# usb_to_uart_swd_bridge.net
KiCad netlist of a schematic drawn in Altium Designer
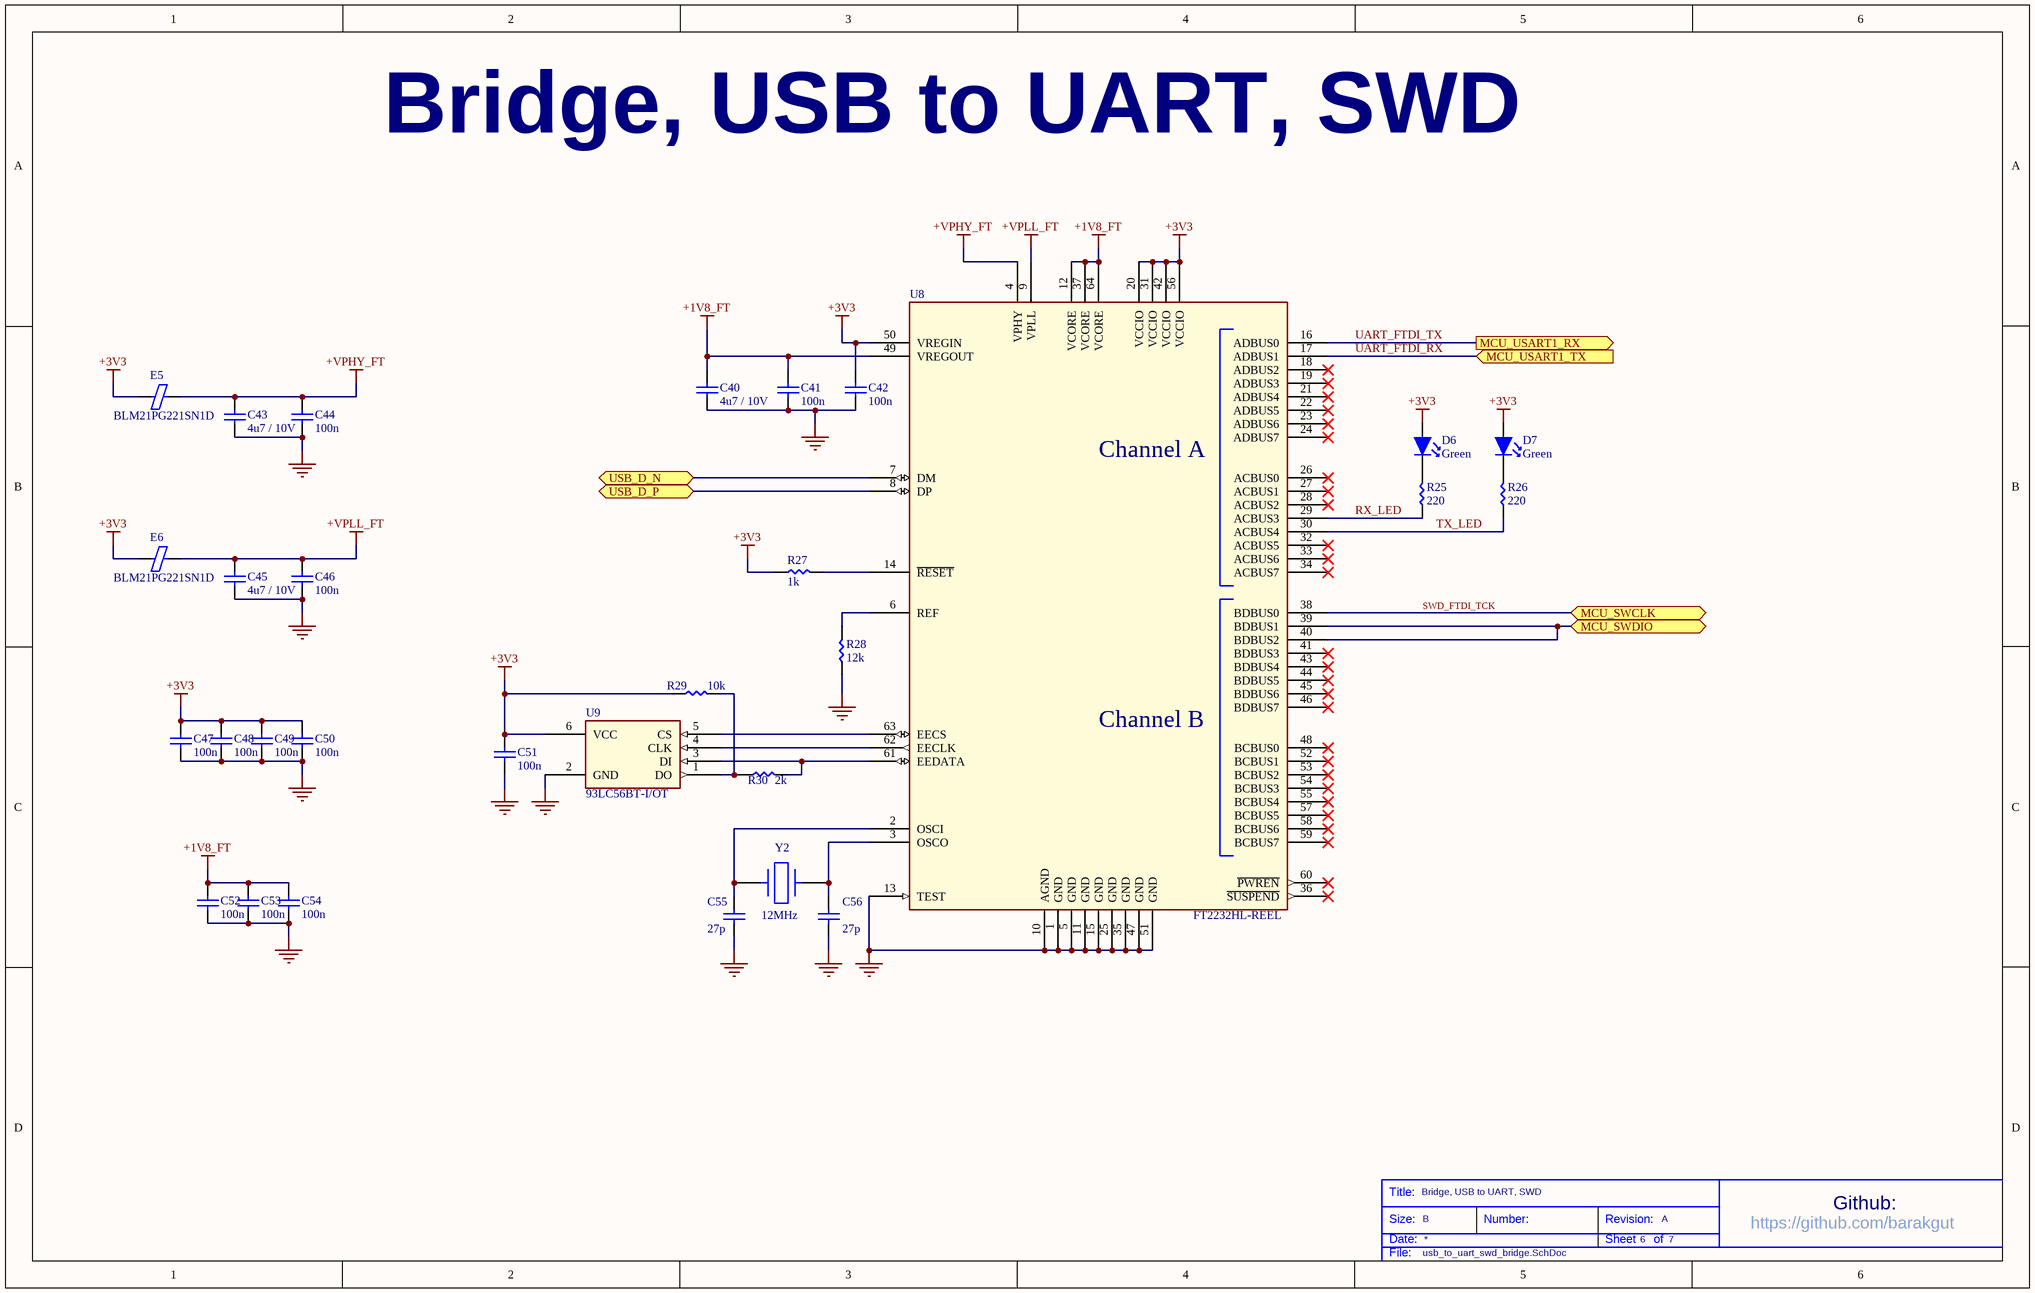
[diagram p0: usb_to_uart_swd_bridge.SchDoc]

(export (version "E")
  (design (tool "Eeschema 10.0.6"))
  (components
    (comp (ref "C40")
      (value "4u7 / 10V")
      (footprint "C0805")
      (fields
        (field (name "MANUFACTURER") "TDK")
        (field (name "TOLERANCE") "±10%")
        (field (name "MANUFACTURER PART NUMBER") "C2012X7R1A475K085AC")
      )
      (libsource (lib "rookieboard_symbols") (part "C2012X7R1A475K085AC"))
    )
    (comp (ref "C41")
      (value "100n")
      (footprint "C0402")
      (fields
        (field (name "MANUFACTURER") "TDK")
        (field (name "PCN PART NUMBER") "MLCC Part Number Change 30/Nov/2012")
        (field (name "TOLERANCE") "±10%")
      )
      (libsource (lib "rookieboard_symbols") (part "CGA2B3X7R1E104K050BB"))
    )
    (comp (ref "C42")
      (value "100n")
      (footprint "C0402")
      (fields
        (field (name "MANUFACTURER") "TDK")
        (field (name "PCN PART NUMBER") "MLCC Part Number Change 30/Nov/2012")
        (field (name "TOLERANCE") "±10%")
      )
      (libsource (lib "rookieboard_symbols") (part "CGA2B3X7R1E104K050BB"))
    )
    (comp (ref "C43")
      (value "4u7 / 10V")
      (footprint "C0805")
      (fields
        (field (name "MANUFACTURER") "TDK")
        (field (name "TOLERANCE") "±10%")
        (field (name "MANUFACTURER PART NUMBER") "C2012X7R1A475K085AC")
      )
      (libsource (lib "rookieboard_symbols") (part "C2012X7R1A475K085AC"))
    )
    (comp (ref "C44")
      (value "100n")
      (footprint "C0402")
      (fields
        (field (name "MANUFACTURER") "TDK")
        (field (name "PCN PART NUMBER") "MLCC Part Number Change 30/Nov/2012")
        (field (name "TOLERANCE") "±10%")
      )
      (libsource (lib "rookieboard_symbols") (part "CGA2B3X7R1E104K050BB"))
    )
    (comp (ref "C45")
      (value "4u7 / 10V")
      (footprint "C0805")
      (fields
        (field (name "MANUFACTURER") "TDK")
        (field (name "TOLERANCE") "±10%")
        (field (name "MANUFACTURER PART NUMBER") "C2012X7R1A475K085AC")
      )
      (libsource (lib "rookieboard_symbols") (part "C2012X7R1A475K085AC"))
    )
    (comp (ref "C46")
      (value "100n")
      (footprint "C0402")
      (fields
        (field (name "MANUFACTURER") "TDK")
        (field (name "PCN PART NUMBER") "MLCC Part Number Change 30/Nov/2012")
        (field (name "TOLERANCE") "±10%")
      )
      (libsource (lib "rookieboard_symbols") (part "CGA2B3X7R1E104K050BB"))
    )
    (comp (ref "C47")
      (value "100n")
      (footprint "C0402")
      (fields
        (field (name "MANUFACTURER") "TDK")
        (field (name "PCN PART NUMBER") "MLCC Part Number Change 30/Nov/2012")
        (field (name "TOLERANCE") "±10%")
      )
      (libsource (lib "rookieboard_symbols") (part "CGA2B3X7R1E104K050BB"))
    )
    (comp (ref "C48")
      (value "100n")
      (footprint "C0402")
      (fields
        (field (name "MANUFACTURER") "TDK")
        (field (name "PCN PART NUMBER") "MLCC Part Number Change 30/Nov/2012")
        (field (name "TOLERANCE") "±10%")
      )
      (libsource (lib "rookieboard_symbols") (part "CGA2B3X7R1E104K050BB"))
    )
    (comp (ref "C49")
      (value "100n")
      (footprint "C0402")
      (fields
        (field (name "MANUFACTURER") "TDK")
        (field (name "PCN PART NUMBER") "MLCC Part Number Change 30/Nov/2012")
        (field (name "TOLERANCE") "±10%")
      )
      (libsource (lib "rookieboard_symbols") (part "CGA2B3X7R1E104K050BB"))
    )
    (comp (ref "C50")
      (value "100n")
      (footprint "C0402")
      (fields
        (field (name "MANUFACTURER") "TDK")
        (field (name "PCN PART NUMBER") "MLCC Part Number Change 30/Nov/2012")
        (field (name "TOLERANCE") "±10%")
      )
      (libsource (lib "rookieboard_symbols") (part "CGA2B3X7R1E104K050BB"))
    )
    (comp (ref "C51")
      (value "100n")
      (footprint "C0402")
      (fields
        (field (name "MANUFACTURER") "TDK")
        (field (name "PCN PART NUMBER") "MLCC Part Number Change 30/Nov/2012")
        (field (name "TOLERANCE") "±10%")
      )
      (libsource (lib "rookieboard_symbols") (part "CGA2B3X7R1E104K050BB"))
    )
    (comp (ref "C52")
      (value "100n")
      (footprint "C0402")
      (fields
        (field (name "MANUFACTURER") "TDK")
        (field (name "PCN PART NUMBER") "MLCC Part Number Change 30/Nov/2012")
        (field (name "TOLERANCE") "±10%")
      )
      (libsource (lib "rookieboard_symbols") (part "CGA2B3X7R1E104K050BB"))
    )
    (comp (ref "C53")
      (value "100n")
      (footprint "C0402")
      (fields
        (field (name "MANUFACTURER") "TDK")
        (field (name "PCN PART NUMBER") "MLCC Part Number Change 30/Nov/2012")
        (field (name "TOLERANCE") "±10%")
      )
      (libsource (lib "rookieboard_symbols") (part "CGA2B3X7R1E104K050BB"))
    )
    (comp (ref "C54")
      (value "100n")
      (footprint "C0402")
      (fields
        (field (name "MANUFACTURER") "TDK")
        (field (name "PCN PART NUMBER") "MLCC Part Number Change 30/Nov/2012")
        (field (name "TOLERANCE") "±10%")
      )
      (libsource (lib "rookieboard_symbols") (part "CGA2B3X7R1E104K050BB"))
    )
    (comp (ref "C55")
      (value "27p")
      (footprint "C0402")
      (fields
        (field (name "MANUFACTURER") "Murata")
        (field (name "MANUFACTURER PART NUMBER") "GJM1555C1H270FB01D")
      )
      (libsource (lib "rookieboard_symbols") (part "GJM1555C1H270FB01D"))
    )
    (comp (ref "C56")
      (value "27p")
      (footprint "C0402")
      (fields
        (field (name "MANUFACTURER") "Murata")
        (field (name "MANUFACTURER PART NUMBER") "GJM1555C1H270FB01D")
      )
      (libsource (lib "rookieboard_symbols") (part "GJM1555C1H270FB01D"))
    )
    (comp (ref "D6")
      (value "Green")
      (footprint "150141VS73100_LED")
      (description "WURTH ELEKTRONIK   150141VS73100   LED, GREEN, 90MCD, 570NM")
      (fields
        (field (name "MANUFACTURER") "Wurth Electronics")
        (field (name "MANUFACTURER PART NUMBER") "150141VS73100")
      )
      (libsource (lib "rookieboard_symbols") (part "150141VS73100"))
    )
    (comp (ref "D7")
      (value "Green")
      (footprint "150141VS73100_LED")
      (description "WURTH ELEKTRONIK   150141VS73100   LED, GREEN, 90MCD, 570NM")
      (fields
        (field (name "MANUFACTURER") "Wurth Electronics")
        (field (name "MANUFACTURER PART NUMBER") "150141VS73100")
      )
      (libsource (lib "rookieboard_symbols") (part "150141VS73100"))
    )
    (comp (ref "E5")
      (value "BLM21PG221SN1D")
      (footprint "R0805")
      (description "FERRITE CHIP 220 OHM 0805")
      (fields (field (name "MANUFACTURER") "Murata"))
      (libsource (lib "rookieboard_symbols") (part "BLM21PG221SN1D"))
    )
    (comp (ref "E6")
      (value "BLM21PG221SN1D")
      (footprint "R0805")
      (description "FERRITE CHIP 220 OHM 0805")
      (fields (field (name "MANUFACTURER") "Murata"))
      (libsource (lib "rookieboard_symbols") (part "BLM21PG221SN1D"))
    )
    (comp (ref "R25")
      (value "220")
      (footprint "R0805")
      (description "Thick Film Resistors - SMD 1/8W 220ohm 1%")
      (fields (field (name "MANUFACTURER") "Yageo") (field (name "TOLERANCE") "1 %"))
      (libsource (lib "rookieboard_symbols") (part "AC0805FR-07220RL"))
    )
    (comp (ref "R26")
      (value "220")
      (footprint "R0805")
      (description "Thick Film Resistors - SMD 1/8W 220ohm 1%")
      (fields (field (name "MANUFACTURER") "Yageo") (field (name "TOLERANCE") "1 %"))
      (libsource (lib "rookieboard_symbols") (part "AC0805FR-07220RL"))
    )
    (comp (ref "R27")
      (value "1k")
      (footprint "R0805")
      (description "RES SMD 1K OHM 1% 1/8W 0805")
      (fields (field (name "MANUFACTURER") "Yageo") (field (name "TOLERANCE") "1 %"))
      (libsource (lib "rookieboard_symbols") (part "RC0805FR-071KL"))
    )
    (comp (ref "R28")
      (value "12k")
      (footprint "R0805")
      (fields
        (field (name "MANUFACTURER") "Yageo")
        (field (name "MANUFACTURER PART NUMBER") "AC0805FR-0712KL")
      )
      (libsource (lib "rookieboard_symbols") (part "AC0805FR-0712KL"))
    )
    (comp (ref "R29")
      (value "10k")
      (footprint "R0805")
      (description "RES SMD 10K OHM 1% 1/8W 0805")
      (fields (field (name "MANUFACTURER") "Yageo") (field (name "TOLERANCE") "1 %"))
      (libsource (lib "rookieboard_symbols") (part "RC0805FR-0710KL"))
    )
    (comp (ref "R30")
      (value "2k")
      (footprint "R0805")
      (description "RES SMD 2K OHM 1% 1/8W 0805")
      (fields (field (name "MANUFACTURER") "Yageo") (field (name "TOLERANCE") "1 %"))
      (libsource (lib "rookieboard_symbols") (part "RC0805FR-072KL"))
    )
    (comp (ref "U8")
      (value "FT2232HL-REEL")
      (footprint "LQFP64")
      (description "IC USB HS DUAL UART/FIFO 64-LQFP")
      (fields (field (name "MANUFACTURER") "FTDI"))
      (libsource (lib "rookieboard_symbols") (part "FT2232HL-REEL"))
    )
    (comp (ref "U9")
      (value "93LC56BT-I/OT")
      (footprint "SOT-23-6")
      (description "EEPROM 128x16")
      (fields (field (name "MANUFACTURER") "Microchip"))
      (libsource (lib "rookieboard_symbols") (part "93LC56BT-I/OT"))
    )
    (comp (ref "Y2")
      (value "12MHz")
      (footprint "ABLS7M2-12.000MHZ-D-2Y-T")
      (description "Crystals 12.0MHz 18pF 30ppm -40C +85C")
      (fields
        (field (name "MANUFACTURER") "Abracon")
        (field (name "MANUFACTURER PART NUMBER") "ABLS7M2-12.000MHZ-D-2Y-T")
      )
      (libsource (lib "rookieboard_symbols") (part "ABLS7M2-12.000MHZ-D-2Y-T"))
    )
  )
  (nets
    (net (code "1") (name "+1V8_FT") (class "Default")
      (node (ref "C40") (pin "2") (pinfunction "2_2") (pintype "passive"))
      (node (ref "C41") (pin "2") (pinfunction "2_2") (pintype "passive"))
      (node (ref "C52") (pin "2") (pinfunction "2_2") (pintype "passive"))
      (node (ref "C53") (pin "2") (pinfunction "2_2") (pintype "passive"))
      (node (ref "C54") (pin "2") (pinfunction "2_2") (pintype "passive"))
      (node (ref "U8") (pin "12") (pinfunction "VCORE_12") (pintype "power_in"))
      (node (ref "U8") (pin "37") (pinfunction "VCORE_37") (pintype "power_in"))
      (node (ref "U8") (pin "49") (pinfunction "VREGOUT_49") (pintype "power_in"))
      (node (ref "U8") (pin "64") (pinfunction "VCORE_64") (pintype "power_in"))
    )
    (net (code "2") (name "+3V3") (class "Default")
      (node (ref "C42") (pin "2") (pinfunction "2_2") (pintype "passive"))
      (node (ref "C47") (pin "2") (pinfunction "2_2") (pintype "passive"))
      (node (ref "C48") (pin "2") (pinfunction "2_2") (pintype "passive"))
      (node (ref "C49") (pin "2") (pinfunction "2_2") (pintype "passive"))
      (node (ref "C50") (pin "2") (pinfunction "2_2") (pintype "passive"))
      (node (ref "C51") (pin "2") (pinfunction "2_2") (pintype "passive"))
      (node (ref "D6") (pin "2") (pinfunction "A_2") (pintype "passive"))
      (node (ref "D7") (pin "2") (pinfunction "A_2") (pintype "passive"))
      (node (ref "E5") (pin "1") (pinfunction "1_1") (pintype "passive"))
      (node (ref "E6") (pin "1") (pinfunction "1_1") (pintype "passive"))
      (node (ref "R27") (pin "1") (pinfunction "1_1") (pintype "passive"))
      (node (ref "R29") (pin "1") (pinfunction "1_1") (pintype "passive"))
      (node (ref "U8") (pin "20") (pinfunction "VCCIO_20") (pintype "power_in"))
      (node (ref "U8") (pin "31") (pinfunction "VCCIO_31") (pintype "power_in"))
      (node (ref "U8") (pin "42") (pinfunction "VCCIO_42") (pintype "power_in"))
      (node (ref "U8") (pin "50") (pinfunction "VREGIN_50") (pintype "power_in"))
      (node (ref "U8") (pin "56") (pinfunction "VCCIO_56") (pintype "power_in"))
      (node (ref "U9") (pin "6") (pinfunction "VCC_6") (pintype "power_in"))
    )
    (net (code "3") (name "+VPHY_FT") (class "Default")
      (node (ref "C43") (pin "2") (pinfunction "2_2") (pintype "passive"))
      (node (ref "C44") (pin "2") (pinfunction "2_2") (pintype "passive"))
      (node (ref "E5") (pin "2") (pinfunction "2_2") (pintype "passive"))
      (node (ref "U8") (pin "4") (pinfunction "VPHY_4") (pintype "power_in"))
    )
    (net (code "4") (name "+VPLL_FT") (class "Default")
      (node (ref "C45") (pin "2") (pinfunction "2_2") (pintype "passive"))
      (node (ref "C46") (pin "2") (pinfunction "2_2") (pintype "passive"))
      (node (ref "E6") (pin "2") (pinfunction "2_2") (pintype "passive"))
      (node (ref "U8") (pin "9") (pinfunction "VPLL_9") (pintype "power_in"))
    )
    (net (code "5") (name "/MCU_SWDIO") (class "Default")
      (node (ref "U8") (pin "39") (pinfunction "BDBUS1_39") (pintype "passive"))
      (node (ref "U8") (pin "40") (pinfunction "BDBUS2_40") (pintype "passive"))
    )
    (net (code "6") (name "/RX_LED") (class "Default")
      (node (ref "R25") (pin "1") (pinfunction "1_1") (pintype "passive"))
      (node (ref "U8") (pin "29") (pinfunction "ACBUS3_29") (pintype "passive"))
    )
    (net (code "7") (name "/SWD_FTDI_TCK") (class "Default")
      (node (ref "U8") (pin "38") (pinfunction "BDBUS0_38") (pintype "passive"))
    )
    (net (code "8") (name "/TX_LED") (class "Default")
      (node (ref "R26") (pin "1") (pinfunction "1_1") (pintype "passive"))
      (node (ref "U8") (pin "30") (pinfunction "ACBUS4_30") (pintype "passive"))
    )
    (net (code "9") (name "/UART_FTDI_RX") (class "Default")
      (node (ref "U8") (pin "17") (pinfunction "ADBUS1_17") (pintype "passive"))
    )
    (net (code "10") (name "/UART_FTDI_TX") (class "Default")
      (node (ref "U8") (pin "16") (pinfunction "ADBUS0_16") (pintype "passive"))
    )
    (net (code "11") (name "/USB_D_N") (class "Default")
      (node (ref "U8") (pin "7") (pinfunction "DM_7") (pintype "bidirectional"))
    )
    (net (code "12") (name "/USB_D_P") (class "Default")
      (node (ref "U8") (pin "8") (pinfunction "DP_8") (pintype "bidirectional"))
    )
    (net (code "13") (name "GND") (class "Default")
      (node (ref "C40") (pin "1") (pinfunction "1_1") (pintype "passive"))
      (node (ref "C41") (pin "1") (pinfunction "1_1") (pintype "passive"))
      (node (ref "C42") (pin "1") (pinfunction "1_1") (pintype "passive"))
      (node (ref "C43") (pin "1") (pinfunction "1_1") (pintype "passive"))
      (node (ref "C44") (pin "1") (pinfunction "1_1") (pintype "passive"))
      (node (ref "C45") (pin "1") (pinfunction "1_1") (pintype "passive"))
      (node (ref "C46") (pin "1") (pinfunction "1_1") (pintype "passive"))
      (node (ref "C47") (pin "1") (pinfunction "1_1") (pintype "passive"))
      (node (ref "C48") (pin "1") (pinfunction "1_1") (pintype "passive"))
      (node (ref "C49") (pin "1") (pinfunction "1_1") (pintype "passive"))
      (node (ref "C50") (pin "1") (pinfunction "1_1") (pintype "passive"))
      (node (ref "C51") (pin "1") (pinfunction "1_1") (pintype "passive"))
      (node (ref "C52") (pin "1") (pinfunction "1_1") (pintype "passive"))
      (node (ref "C53") (pin "1") (pinfunction "1_1") (pintype "passive"))
      (node (ref "C54") (pin "1") (pinfunction "1_1") (pintype "passive"))
      (node (ref "C55") (pin "1") (pinfunction "1_1") (pintype "passive"))
      (node (ref "C56") (pin "1") (pinfunction "1_1") (pintype "passive"))
      (node (ref "R28") (pin "1") (pinfunction "1_1") (pintype "passive"))
      (node (ref "U8") (pin "1") (pinfunction "GND_1") (pintype "power_in"))
      (node (ref "U8") (pin "10") (pinfunction "AGND_10") (pintype "power_in"))
      (node (ref "U8") (pin "11") (pinfunction "GND_11") (pintype "power_in"))
      (node (ref "U8") (pin "13") (pinfunction "TEST_13") (pintype "input"))
      (node (ref "U8") (pin "15") (pinfunction "GND_15") (pintype "power_in"))
      (node (ref "U8") (pin "25") (pinfunction "GND_25") (pintype "power_in"))
      (node (ref "U8") (pin "35") (pinfunction "GND_35") (pintype "power_in"))
      (node (ref "U8") (pin "47") (pinfunction "GND_47") (pintype "power_in"))
      (node (ref "U8") (pin "5") (pinfunction "GND_5") (pintype "power_in"))
      (node (ref "U8") (pin "51") (pinfunction "GND_51") (pintype "power_in"))
      (node (ref "U9") (pin "2") (pinfunction "GND_2") (pintype "power_in"))
    )
    (net (code "14") (name "Net-(D6-K)") (class "Default")
      (node (ref "D6") (pin "1") (pinfunction "K_1") (pintype "passive"))
      (node (ref "R25") (pin "2") (pinfunction "2_2") (pintype "passive"))
    )
    (net (code "15") (name "Net-(D7-K)") (class "Default")
      (node (ref "D7") (pin "1") (pinfunction "K_1") (pintype "passive"))
      (node (ref "R26") (pin "2") (pinfunction "2_2") (pintype "passive"))
    )
    (net (code "16") (name "Net-(U8-EECLK)") (class "Default")
      (node (ref "U8") (pin "62") (pinfunction "EECLK_62") (pintype "output"))
      (node (ref "U9") (pin "4") (pinfunction "CLK_4") (pintype "input"))
    )
    (net (code "17") (name "Net-(U8-EECS)") (class "Default")
      (node (ref "U8") (pin "63") (pinfunction "EECS_63") (pintype "bidirectional"))
      (node (ref "U9") (pin "5") (pinfunction "CS_5") (pintype "input"))
    )
    (net (code "18") (name "Net-(U8-EEDATA)") (class "Default")
      (node (ref "R30") (pin "2") (pinfunction "2_2") (pintype "passive"))
      (node (ref "U8") (pin "61") (pinfunction "EEDATA_61") (pintype "bidirectional"))
      (node (ref "U9") (pin "3") (pinfunction "DI_3") (pintype "input"))
    )
    (net (code "19") (name "Net-(U8-OSCI)") (class "Default")
      (node (ref "C55") (pin "2") (pinfunction "2_2") (pintype "passive"))
      (node (ref "U8") (pin "2") (pinfunction "OSCI_2") (pintype "passive"))
      (node (ref "Y2") (pin "2") (pinfunction "2_2") (pintype "passive"))
    )
    (net (code "20") (name "Net-(U8-OSCO)") (class "Default")
      (node (ref "C56") (pin "2") (pinfunction "2_2") (pintype "passive"))
      (node (ref "U8") (pin "3") (pinfunction "OSCO_3") (pintype "passive"))
      (node (ref "Y2") (pin "1") (pinfunction "1_1") (pintype "passive"))
    )
    (net (code "21") (name "Net-(U8-REF)") (class "Default")
      (node (ref "R28") (pin "2") (pinfunction "2_2") (pintype "passive"))
      (node (ref "U8") (pin "6") (pinfunction "REF_6") (pintype "passive"))
    )
    (net (code "22") (name "Net-(U8-~{RESET})") (class "Default")
      (node (ref "R27") (pin "2") (pinfunction "2_2") (pintype "passive"))
      (node (ref "U8") (pin "14") (pinfunction "~{RESET}_14") (pintype "passive"))
    )
    (net (code "23") (name "Net-(U9-DO)") (class "Default")
      (node (ref "R29") (pin "2") (pinfunction "2_2") (pintype "passive"))
      (node (ref "R30") (pin "1") (pinfunction "1_1") (pintype "passive"))
      (node (ref "U9") (pin "1") (pinfunction "DO_1") (pintype "output"))
    )
    (net (code "24") (name "unconnected-(U8-ACBUS0-Pad26)") (class "Default")
      (node (ref "U8") (pin "26") (pinfunction "ACBUS0_26") (pintype "passive+no_connect"))
    )
    (net (code "25") (name "unconnected-(U8-ACBUS1-Pad27)") (class "Default")
      (node (ref "U8") (pin "27") (pinfunction "ACBUS1_27") (pintype "passive+no_connect"))
    )
    (net (code "26") (name "unconnected-(U8-ACBUS2-Pad28)") (class "Default")
      (node (ref "U8") (pin "28") (pinfunction "ACBUS2_28") (pintype "passive+no_connect"))
    )
    (net (code "27") (name "unconnected-(U8-ACBUS5-Pad32)") (class "Default")
      (node (ref "U8") (pin "32") (pinfunction "ACBUS5_32") (pintype "passive+no_connect"))
    )
    (net (code "28") (name "unconnected-(U8-ACBUS6-Pad33)") (class "Default")
      (node (ref "U8") (pin "33") (pinfunction "ACBUS6_33") (pintype "passive+no_connect"))
    )
    (net (code "29") (name "unconnected-(U8-ACBUS7-Pad34)") (class "Default")
      (node (ref "U8") (pin "34") (pinfunction "ACBUS7_34") (pintype "passive+no_connect"))
    )
    (net (code "30") (name "unconnected-(U8-ADBUS2-Pad18)") (class "Default")
      (node (ref "U8") (pin "18") (pinfunction "ADBUS2_18") (pintype "passive+no_connect"))
    )
    (net (code "31") (name "unconnected-(U8-ADBUS3-Pad19)") (class "Default")
      (node (ref "U8") (pin "19") (pinfunction "ADBUS3_19") (pintype "passive+no_connect"))
    )
    (net (code "32") (name "unconnected-(U8-ADBUS4-Pad21)") (class "Default")
      (node (ref "U8") (pin "21") (pinfunction "ADBUS4_21") (pintype "passive+no_connect"))
    )
    (net (code "33") (name "unconnected-(U8-ADBUS5-Pad22)") (class "Default")
      (node (ref "U8") (pin "22") (pinfunction "ADBUS5_22") (pintype "passive+no_connect"))
    )
    (net (code "34") (name "unconnected-(U8-ADBUS6-Pad23)") (class "Default")
      (node (ref "U8") (pin "23") (pinfunction "ADBUS6_23") (pintype "passive+no_connect"))
    )
    (net (code "35") (name "unconnected-(U8-ADBUS7-Pad24)") (class "Default")
      (node (ref "U8") (pin "24") (pinfunction "ADBUS7_24") (pintype "passive+no_connect"))
    )
    (net (code "36") (name "unconnected-(U8-BCBUS0-Pad48)") (class "Default")
      (node (ref "U8") (pin "48") (pinfunction "BCBUS0_48") (pintype "passive+no_connect"))
    )
    (net (code "37") (name "unconnected-(U8-BCBUS1-Pad52)") (class "Default")
      (node (ref "U8") (pin "52") (pinfunction "BCBUS1_52") (pintype "passive+no_connect"))
    )
    (net (code "38") (name "unconnected-(U8-BCBUS2-Pad53)") (class "Default")
      (node (ref "U8") (pin "53") (pinfunction "BCBUS2_53") (pintype "passive+no_connect"))
    )
    (net (code "39") (name "unconnected-(U8-BCBUS3-Pad54)") (class "Default")
      (node (ref "U8") (pin "54") (pinfunction "BCBUS3_54") (pintype "passive+no_connect"))
    )
    (net (code "40") (name "unconnected-(U8-BCBUS4-Pad55)") (class "Default")
      (node (ref "U8") (pin "55") (pinfunction "BCBUS4_55") (pintype "passive+no_connect"))
    )
    (net (code "41") (name "unconnected-(U8-BCBUS5-Pad57)") (class "Default")
      (node (ref "U8") (pin "57") (pinfunction "BCBUS5_57") (pintype "passive+no_connect"))
    )
    (net (code "42") (name "unconnected-(U8-BCBUS6-Pad58)") (class "Default")
      (node (ref "U8") (pin "58") (pinfunction "BCBUS6_58") (pintype "passive+no_connect"))
    )
    (net (code "43") (name "unconnected-(U8-BCBUS7-Pad59)") (class "Default")
      (node (ref "U8") (pin "59") (pinfunction "BCBUS7_59") (pintype "passive+no_connect"))
    )
    (net (code "44") (name "unconnected-(U8-BDBUS3-Pad41)") (class "Default")
      (node (ref "U8") (pin "41") (pinfunction "BDBUS3_41") (pintype "passive+no_connect"))
    )
    (net (code "45") (name "unconnected-(U8-BDBUS4-Pad43)") (class "Default")
      (node (ref "U8") (pin "43") (pinfunction "BDBUS4_43") (pintype "passive+no_connect"))
    )
    (net (code "46") (name "unconnected-(U8-BDBUS5-Pad44)") (class "Default")
      (node (ref "U8") (pin "44") (pinfunction "BDBUS5_44") (pintype "passive+no_connect"))
    )
    (net (code "47") (name "unconnected-(U8-BDBUS6-Pad45)") (class "Default")
      (node (ref "U8") (pin "45") (pinfunction "BDBUS6_45") (pintype "passive+no_connect"))
    )
    (net (code "48") (name "unconnected-(U8-BDBUS7-Pad46)") (class "Default")
      (node (ref "U8") (pin "46") (pinfunction "BDBUS7_46") (pintype "passive+no_connect"))
    )
    (net (code "49") (name "unconnected-(U8-~{PWREN}-Pad60)") (class "Default")
      (node (ref "U8") (pin "60") (pinfunction "~{PWREN}_60") (pintype "output+no_connect"))
    )
    (net (code "50") (name "unconnected-(U8-~{SUSPEND}-Pad36)") (class "Default")
      (node (ref "U8") (pin "36") (pinfunction "~{SUSPEND}_36") (pintype "output+no_connect"))
    )
  )
)
